# SIM7020_mp2128.net
KiCad netlist of a schematic drawn in Altium Designer
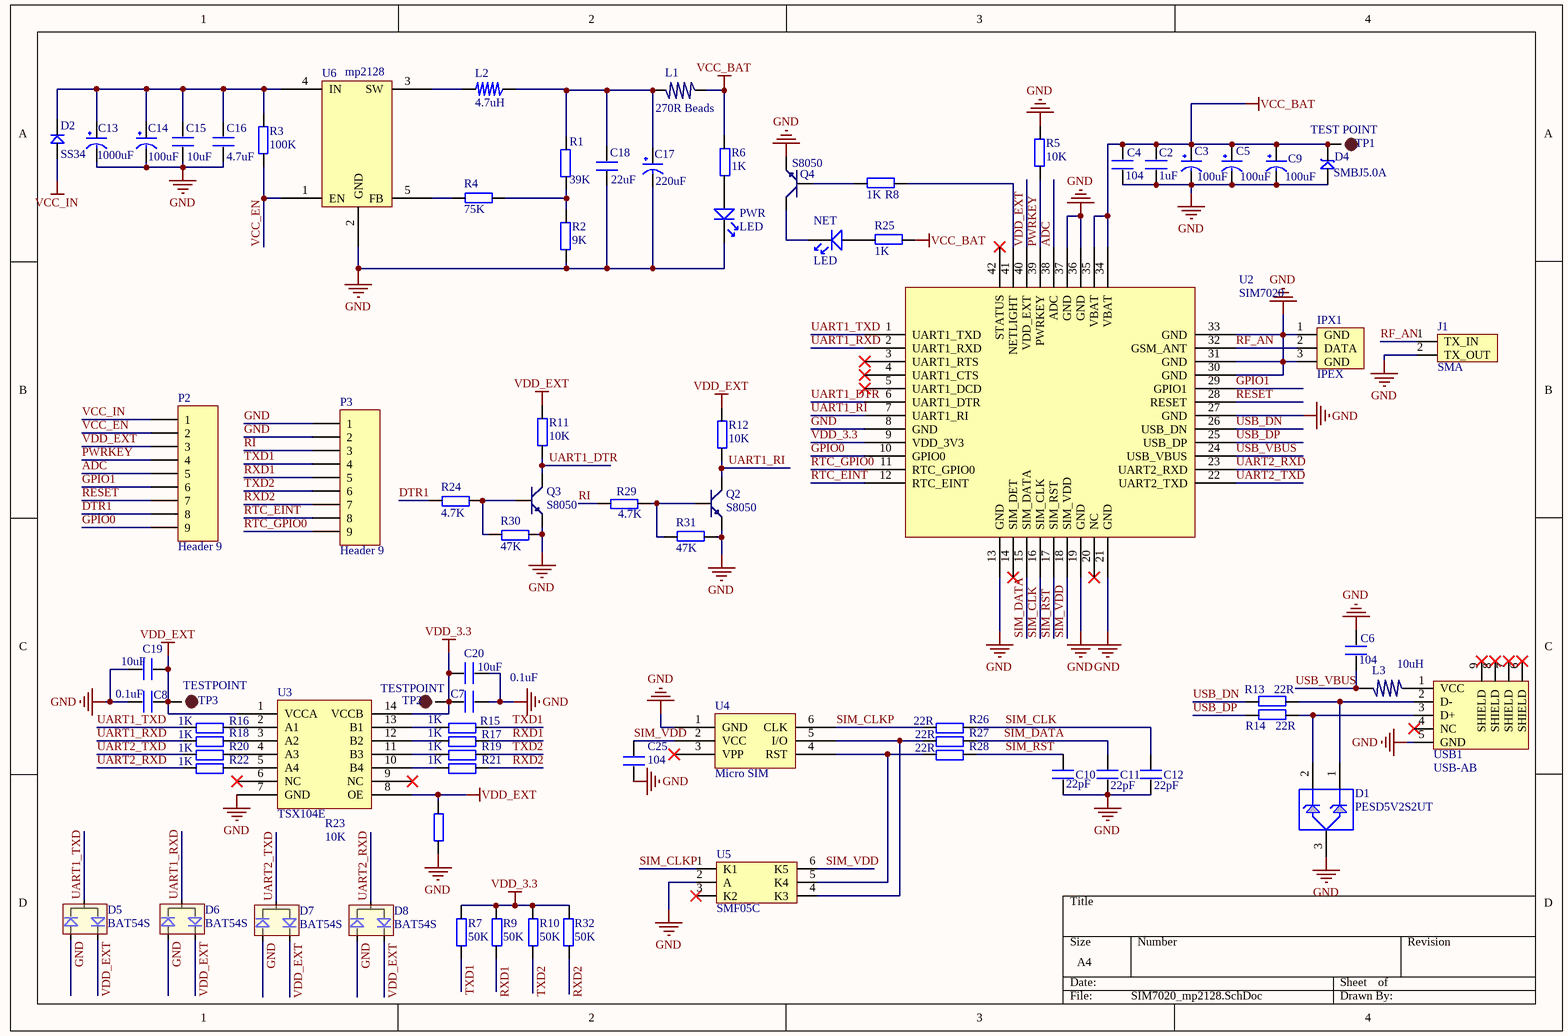
[diagram p0: SIM7020_mp2128.SchDoc]

(export (version "E")
  (design (tool "Eeschema 10.0.6"))
  (components
    (comp (ref "C2") (value "1uF") (footprint "0603P") (libsource (lib "SIM7020") (part "C")))
    (comp (ref "C3") (value "100uF") (footprint "C3528") (libsource (lib "SIM7020") (part "CAP")))
    (comp (ref "C4") (value "104") (footprint "0603P") (libsource (lib "ALIENTEK_COMPONENT") (part "C")))
    (comp (ref "C5") (value "100uF") (footprint "C3528") (libsource (lib "SIM7020") (part "CAP")))
    (comp (ref "C6") (value "104") (footprint "0603P") (libsource (lib "ALIENTEK_COMPONENT") (part "C")))
    (comp (ref "C7") (value "0.1uF") (footprint "0603P") (libsource (lib "SIM7020") (part "C")))
    (comp (ref "C8") (value "0.1uF") (footprint "0603P") (libsource (lib "SIM7020") (part "C")))
    (comp (ref "C9") (value "100uF") (footprint "C3528") (libsource (lib "SIM7020") (part "CAP")))
    (comp (ref "C10") (value "22pF") (footprint "0402") (libsource (lib "ALIENTEK_COMPONENT") (part "C")))
    (comp (ref "C11") (value "22pF") (footprint "0402") (libsource (lib "ALIENTEK_COMPONENT") (part "C")))
    (comp (ref "C12") (value "22pF") (footprint "0402") (libsource (lib "ALIENTEK_COMPONENT") (part "C")))
    (comp (ref "C13")
      (value "1000uF")
      (footprint "CAP2.54")
      (libsource (lib "ALIENTEK_COMPONENT") (part "CAP"))
    )
    (comp (ref "C14") (value "100uF") (footprint "C3528") (libsource (lib "ALIENTEK_COMPONENT") (part "CAP")))
    (comp (ref "C15") (value "10uF") (footprint "0805") (libsource (lib "SIM7020") (part "C")))
    (comp (ref "C16") (value "4.7uF") (footprint "0603P") (libsource (lib "SIM7020") (part "C")))
    (comp (ref "C17") (value "220uF") (footprint "CC6.56.5") (libsource (lib "SIM7020") (part "CAP")))
    (comp (ref "C18") (value "22uF") (footprint "1206") (libsource (lib "SIM7020") (part "C")))
    (comp (ref "C19") (value "10uF") (footprint "0603P") (libsource (lib "SIM7020") (part "C")))
    (comp (ref "C20") (value "10uF") (footprint "0603P") (libsource (lib "SIM7020") (part "C")))
    (comp (ref "C25") (value "104") (footprint "0603P") (libsource (lib "ALIENTEK_COMPONENT") (part "C")))
    (comp (ref "D1")
      (value "PESD5V2S2UT")
      (footprint "SOT-23")
      (description "PESD5V2S2UT,SOT-23,NXP")
      (fields (field (name "Comment") "ESD-3"))
      (libsource (lib "02.MCU_KL25") (part "ESD-3"))
    )
    (comp (ref "D2")
      (value "SS34")
      (footprint "DIODE_3*5.3")
      (description "1N4148")
      (libsource (lib "alientek_sch_lib") (part "D"))
    )
    (comp (ref "D4")
      (value "SMBJ5.0A")
      (footprint "SMBJ")
      (description "TVS")
      (libsource (lib "ALIENTEK_COMPONENT") (part "SMBJ"))
    )
    (comp (ref "D5")
      (value "BAT54S")
      (footprint "SOT-23")
      (description "双肖特基二极管")
      (libsource (lib "ALIENTEK_COMPONENT") (part "BAT54S"))
    )
    (comp (ref "D6")
      (value "BAT54S")
      (footprint "SOT-23")
      (description "双肖特基二极管")
      (libsource (lib "ALIENTEK_COMPONENT") (part "BAT54S"))
    )
    (comp (ref "D7")
      (value "BAT54S")
      (footprint "SOT-23")
      (description "双肖特基二极管")
      (libsource (lib "ALIENTEK_COMPONENT") (part "BAT54S"))
    )
    (comp (ref "D8")
      (value "BAT54S")
      (footprint "SOT-23")
      (description "双肖特基二极管")
      (libsource (lib "ALIENTEK_COMPONENT") (part "BAT54S"))
    )
    (comp (ref "IPX1")
      (value "IPEX")
      (footprint "IPEX")
      (description "IPEX座")
      (libsource (lib "ATK_S1216F8_BD_V1.1") (part "IPEX"))
    )
    (comp (ref "J1")
      (value "SMA")
      (footprint "SMA-2")
      (description "SMA-2")
      (libsource (lib "SIM7020") (part "SMA-2"))
    )
    (comp (ref "L1") (value "270R Beads") (footprint "1206") (libsource (lib "SIM7020") (part "L")))
    (comp (ref "L2")
      (value "4.7uH")
      (footprint "L_CD43")
      (libsource (lib "ATK-7'TFTLCD电容触摸屏模块_V2.2") (part "L_SOP"))
    )
    (comp (ref "L3") (value "10uH") (footprint "0805") (libsource (lib "ALIENTEK_COMPONENT") (part "L")))
    (comp (ref "NET") (value "LED") (footprint "SMDLED") (libsource (lib "SIM7020") (part "LED")))
    (comp (ref "P2")
      (value "Header 9")
      (footprint "HDR1X9")
      (description "Header, 9-Pin")
      (fields (field (name "PUBLISHER") "Altium Limited"))
      (libsource (lib "Miscellaneous Connectors") (part "Header 9"))
    )
    (comp (ref "P3")
      (value "Header 9")
      (footprint "HDR1X9")
      (description "Header, 9-Pin")
      (fields (field (name "PUBLISHER") "Altium Limited"))
      (libsource (lib "Miscellaneous Connectors") (part "Header 9"))
    )
    (comp (ref "PWR") (value "LED") (footprint "SMDLED") (libsource (lib "SIM7020") (part "LED")))
    (comp (ref "Q2")
      (value "S8050")
      (footprint "SOT-23R")
      (description "8050/BCW846/BCW847")
      (libsource (lib "SIM7020") (part "NPN"))
    )
    (comp (ref "Q3")
      (value "S8050")
      (footprint "SOT-23R")
      (description "8050/BCW846/BCW847")
      (libsource (lib "SIM7020") (part "NPN"))
    )
    (comp (ref "Q4")
      (value "S8050")
      (footprint "SOT-23R")
      (description "8050/BCW846/BCW847")
      (libsource (lib "SIM7020") (part "NPN"))
    )
    (comp (ref "R1") (value "39K") (footprint "0603P") (libsource (lib "ALIENTEK_COMPONENT") (part "R")))
    (comp (ref "R2") (value "9K") (footprint "0603P") (libsource (lib "ALIENTEK_COMPONENT") (part "R")))
    (comp (ref "R3") (value "100K") (footprint "0603P") (libsource (lib "ALIENTEK_COMPONENT") (part "R")))
    (comp (ref "R4") (value "75K") (footprint "0603P") (libsource (lib "ALIENTEK_COMPONENT") (part "R")))
    (comp (ref "R5") (value "10K") (footprint "0603P") (libsource (lib "ALIENTEK_COMPONENT") (part "R")))
    (comp (ref "R6") (value "1K") (footprint "0603P") (libsource (lib "ALIENTEK_COMPONENT") (part "R")))
    (comp (ref "R7") (value "50K") (footprint "0603P") (libsource (lib "SIM7020") (part "R")))
    (comp (ref "R8") (value "1K") (footprint "0603P") (libsource (lib "ALIENTEK_COMPONENT") (part "R")))
    (comp (ref "R9") (value "50K") (footprint "0603P") (libsource (lib "SIM7020") (part "R")))
    (comp (ref "R10") (value "50K") (footprint "0603P") (libsource (lib "SIM7020") (part "R")))
    (comp (ref "R11") (value "10K") (footprint "0603P") (libsource (lib "ALIENTEK_COMPONENT") (part "R")))
    (comp (ref "R12") (value "10K") (footprint "0603P") (libsource (lib "ALIENTEK_COMPONENT") (part "R")))
    (comp (ref "R13") (value "22R") (footprint "0603P") (libsource (lib "SIM7020") (part "R")))
    (comp (ref "R14") (value "22R") (footprint "0603P") (libsource (lib "SIM7020") (part "R")))
    (comp (ref "R15") (value "1K") (footprint "0603P") (libsource (lib "SIM7020") (part "R")))
    (comp (ref "R16") (value "1K") (footprint "0603P") (libsource (lib "SIM7020") (part "R")))
    (comp (ref "R17") (value "1K") (footprint "0603P") (libsource (lib "SIM7020") (part "R")))
    (comp (ref "R18") (value "1K") (footprint "0603P") (libsource (lib "SIM7020") (part "R")))
    (comp (ref "R19") (value "1K") (footprint "0603P") (libsource (lib "SIM7020") (part "R")))
    (comp (ref "R20") (value "1K") (footprint "0603P") (libsource (lib "SIM7020") (part "R")))
    (comp (ref "R21") (value "1K") (footprint "0603P") (libsource (lib "SIM7020") (part "R")))
    (comp (ref "R22") (value "1K") (footprint "0603P") (libsource (lib "SIM7020") (part "R")))
    (comp (ref "R23") (value "10K") (footprint "0603P") (libsource (lib "SIM7020") (part "R")))
    (comp (ref "R24") (value "4.7K") (footprint "0603P") (libsource (lib "ALIENTEK_COMPONENT") (part "R")))
    (comp (ref "R25") (value "1K") (footprint "0603P") (libsource (lib "ALIENTEK_COMPONENT") (part "R")))
    (comp (ref "R26") (value "22R") (footprint "0603P") (libsource (lib "SIM7020") (part "R")))
    (comp (ref "R27") (value "22R") (footprint "0603P") (libsource (lib "SIM7020") (part "R")))
    (comp (ref "R28") (value "22R") (footprint "0603P") (libsource (lib "SIM7020") (part "R")))
    (comp (ref "R29") (value "4.7K") (footprint "0603P") (libsource (lib "ALIENTEK_COMPONENT") (part "R")))
    (comp (ref "R30") (value "47K") (footprint "0603P") (libsource (lib "ALIENTEK_COMPONENT") (part "R")))
    (comp (ref "R31") (value "47K") (footprint "0603P") (libsource (lib "ALIENTEK_COMPONENT") (part "R")))
    (comp (ref "R32") (value "50K") (footprint "0603P") (libsource (lib "SIM7020") (part "R")))
    (comp (ref "TP1")
      (value "TEST POINT")
      (footprint "TP-1.5")
      (description "测试点")
      (libsource (lib "ALIENTEK_COMPONENT") (part "TEST-POINT"))
    )
    (comp (ref "TP2")
      (value "TESTPOINT")
      (footprint "TP-1.5")
      (description "测试点")
      (libsource (lib "ALIENTEK_COMPONENT") (part "TEST-POINT"))
    )
    (comp (ref "TP3")
      (value "TESTPOINT")
      (footprint "TP-1.5")
      (description "测试点")
      (libsource (lib "ALIENTEK_COMPONENT") (part "TEST-POINT"))
    )
    (comp (ref "U2")
      (value "SIM7020")
      (footprint "SIM7020")
      (description "NBloT")
      (libsource (lib "SIM7020") (part "SIM7020"))
    )
    (comp (ref "U3") (value "TSX104E") (footprint "TSX104E") (libsource (lib "SIM7020") (part "TSX104E")))
    (comp (ref "U4") (value "Micro SIM") (footprint "Micro SIM") (libsource (lib "plib") (part "Micro SIM")))
    (comp (ref "U5")
      (value "SMF05C")
      (footprint "SMF05C")
      (description "TVS")
      (libsource (lib "plib") (part "SMF05C"))
    )
    (comp (ref "U6") (value "mp2128") (footprint "SOT-23-5") (libsource (lib "SIM7020") (part "mp2128")))
    (comp (ref "USB1")
      (value "USB-AB")
      (footprint "USB_AB")
      (description "MicroUSB")
      (libsource (lib "ALIENTEK_COMPONENT") (part "USB-AB"))
    )
  )
  (nets
    (net (code "1") (name "/ADC") (class "Default")
      (node (ref "P2") (pin "5") (pinfunction "5_5") (pintype "passive"))
      (node (ref "U2") (pin "38") (pinfunction "ADC_38") (pintype "passive"))
    )
    (net (code "2") (name "/DTR1") (class "Default")
      (node (ref "P2") (pin "8") (pinfunction "8_8") (pintype "passive"))
      (node (ref "R24") (pin "1") (pintype "passive"))
    )
    (net (code "3") (name "/GPIO0") (class "Default")
      (node (ref "P2") (pin "9") (pinfunction "9_9") (pintype "passive"))
      (node (ref "U2") (pin "10") (pinfunction "GPIO0_10") (pintype "passive"))
    )
    (net (code "4") (name "/GPIO1") (class "Default")
      (node (ref "P2") (pin "6") (pinfunction "6_6") (pintype "passive"))
      (node (ref "U2") (pin "29") (pinfunction "GPIO1_29") (pintype "passive"))
    )
    (net (code "5") (name "/PWRKEY") (class "Default")
      (node (ref "P2") (pin "4") (pinfunction "4_4") (pintype "passive"))
      (node (ref "R5") (pin "2") (pintype "passive"))
      (node (ref "U2") (pin "39") (pinfunction "PWRKEY_39") (pintype "passive"))
    )
    (net (code "6") (name "/RESET") (class "Default")
      (node (ref "P2") (pin "7") (pinfunction "7_7") (pintype "passive"))
      (node (ref "U2") (pin "28") (pinfunction "RESET_28") (pintype "passive"))
    )
    (net (code "7") (name "/RF_AN") (class "Default")
      (node (ref "IPX1") (pin "2") (pinfunction "DATA_2") (pintype "passive"))
      (node (ref "J1") (pin "1") (pinfunction "TX_IN_1") (pintype "passive"))
      (node (ref "U2") (pin "32") (pinfunction "GSM_ANT_32") (pintype "passive"))
    )
    (net (code "8") (name "/RI") (class "Default")
      (node (ref "P3") (pin "3") (pinfunction "3_3") (pintype "passive"))
      (node (ref "R29") (pin "1") (pintype "passive"))
    )
    (net (code "9") (name "/RTC_EINT") (class "Default")
      (node (ref "P3") (pin "8") (pinfunction "8_8") (pintype "passive"))
      (node (ref "U2") (pin "12") (pinfunction "RTC_EINT_12") (pintype "passive"))
    )
    (net (code "10") (name "/RTC_GPIO0") (class "Default")
      (node (ref "P3") (pin "9") (pinfunction "9_9") (pintype "passive"))
      (node (ref "U2") (pin "11") (pinfunction "RTC_GPIO0_11") (pintype "passive"))
    )
    (net (code "11") (name "/RXD1") (class "Default")
      (node (ref "P3") (pin "5") (pinfunction "5_5") (pintype "passive"))
      (node (ref "R17") (pin "2") (pintype "passive"))
      (node (ref "R9") (pin "1") (pintype "passive"))
    )
    (net (code "12") (name "/RXD2") (class "Default")
      (node (ref "P3") (pin "7") (pinfunction "7_7") (pintype "passive"))
      (node (ref "R21") (pin "2") (pintype "passive"))
      (node (ref "R32") (pin "2") (pintype "passive"))
    )
    (net (code "13") (name "/SIM_CLK") (class "Default")
      (node (ref "C12") (pin "2") (pintype "passive"))
      (node (ref "R26") (pin "2") (pintype "passive"))
      (node (ref "U2") (pin "16") (pinfunction "SIM_CLK_16") (pintype "passive"))
    )
    (net (code "14") (name "/SIM_CLKP") (class "Default")
      (node (ref "R26") (pin "1") (pintype "passive"))
      (node (ref "U4") (pin "6") (pinfunction "CLK_6") (pintype "passive"))
      (node (ref "U5") (pin "1") (pinfunction "K1_1") (pintype "passive"))
    )
    (net (code "15") (name "/SIM_DATA") (class "Default")
      (node (ref "C11") (pin "2") (pintype "passive"))
      (node (ref "R27") (pin "2") (pintype "passive"))
      (node (ref "U2") (pin "15") (pinfunction "SIM_DATA_15") (pintype "passive"))
    )
    (net (code "16") (name "/SIM_RST") (class "Default")
      (node (ref "C10") (pin "1") (pintype "passive"))
      (node (ref "R28") (pin "2") (pintype "passive"))
      (node (ref "U2") (pin "17") (pinfunction "SIM_RST_17") (pintype "passive"))
    )
    (net (code "17") (name "/SIM_VDD") (class "Default")
      (node (ref "C25") (pin "2") (pintype "passive"))
      (node (ref "U2") (pin "18") (pinfunction "SIM_VDD_18") (pintype "passive"))
      (node (ref "U4") (pin "2") (pinfunction "VCC_2") (pintype "passive"))
      (node (ref "U5") (pin "6") (pinfunction "K5_6") (pintype "passive"))
    )
    (net (code "18") (name "/TXD1") (class "Default")
      (node (ref "P3") (pin "4") (pinfunction "4_4") (pintype "passive"))
      (node (ref "R15") (pin "2") (pintype "passive"))
      (node (ref "R7") (pin "1") (pintype "passive"))
    )
    (net (code "19") (name "/TXD2") (class "Default")
      (node (ref "P3") (pin "6") (pinfunction "6_6") (pintype "passive"))
      (node (ref "R10") (pin "1") (pintype "passive"))
      (node (ref "R19") (pin "2") (pintype "passive"))
    )
    (net (code "20") (name "/UART1_DTR") (class "Default")
      (node (ref "Q3") (pin "3") (pinfunction "C_3") (pintype "passive"))
      (node (ref "R11") (pin "1") (pintype "passive"))
      (node (ref "U2") (pin "6") (pinfunction "UART1_DTR_6") (pintype "passive"))
    )
    (net (code "21") (name "/UART1_RI") (class "Default")
      (node (ref "Q2") (pin "3") (pinfunction "C_3") (pintype "passive"))
      (node (ref "R12") (pin "1") (pintype "passive"))
      (node (ref "U2") (pin "7") (pinfunction "UART1_RI_7") (pintype "passive"))
    )
    (net (code "22") (name "/UART1_RXD") (class "Default")
      (node (ref "D6") (pin "3") (pintype "passive"))
      (node (ref "R18") (pin "1") (pintype "passive"))
      (node (ref "U2") (pin "2") (pinfunction "UART1_RXD_2") (pintype "passive"))
    )
    (net (code "23") (name "/UART1_TXD") (class "Default")
      (node (ref "D5") (pin "3") (pintype "passive"))
      (node (ref "R16") (pin "1") (pintype "passive"))
      (node (ref "U2") (pin "1") (pinfunction "UART1_TXD_1") (pintype "passive"))
    )
    (net (code "24") (name "/UART2_RXD") (class "Default")
      (node (ref "D8") (pin "3") (pintype "passive"))
      (node (ref "R22") (pin "1") (pintype "passive"))
      (node (ref "U2") (pin "23") (pinfunction "UART2_RXD_23") (pintype "passive"))
    )
    (net (code "25") (name "/UART2_TXD") (class "Default")
      (node (ref "D7") (pin "3") (pintype "passive"))
      (node (ref "R20") (pin "1") (pintype "passive"))
      (node (ref "U2") (pin "22") (pinfunction "UART2_TXD_22") (pintype "passive"))
    )
    (net (code "26") (name "/USB_DN") (class "Default")
      (node (ref "R13") (pin "2") (pintype "passive"))
      (node (ref "U2") (pin "26") (pinfunction "USB_DN_26") (pintype "passive"))
    )
    (net (code "27") (name "/USB_DP") (class "Default")
      (node (ref "R14") (pin "2") (pintype "passive"))
      (node (ref "U2") (pin "25") (pinfunction "USB_DP_25") (pintype "passive"))
    )
    (net (code "28") (name "/USB_VBUS") (class "Default")
      (node (ref "C6") (pin "1") (pintype "passive"))
      (node (ref "L3") (pin "2") (pintype "passive"))
      (node (ref "U2") (pin "24") (pinfunction "USB_VBUS_24") (pintype "passive"))
    )
    (net (code "29") (name "/VCC_EN") (class "Default")
      (node (ref "P2") (pin "2") (pinfunction "2_2") (pintype "passive"))
      (node (ref "R3") (pin "2") (pintype "passive"))
      (node (ref "U6") (pin "1") (pinfunction "EN_1") (pintype "passive"))
    )
    (net (code "30") (name "GND") (class "Default")
      (node (ref "C10") (pin "2") (pintype "passive"))
      (node (ref "C11") (pin "1") (pintype "passive"))
      (node (ref "C12") (pin "1") (pintype "passive"))
      (node (ref "C13") (pin "2") (pinfunction "GND_2") (pintype "passive"))
      (node (ref "C14") (pin "2") (pinfunction "GND_2") (pintype "passive"))
      (node (ref "C15") (pin "2") (pintype "passive"))
      (node (ref "C16") (pin "1") (pintype "passive"))
      (node (ref "C17") (pin "2") (pinfunction "GND_2") (pintype "passive"))
      (node (ref "C18") (pin "1") (pintype "passive"))
      (node (ref "C19") (pin "2") (pintype "passive"))
      (node (ref "C2") (pin "1") (pintype "passive"))
      (node (ref "C20") (pin "2") (pintype "passive"))
      (node (ref "C25") (pin "1") (pintype "passive"))
      (node (ref "C3") (pin "2") (pinfunction "GND_2") (pintype "passive"))
      (node (ref "C4") (pin "1") (pintype "passive"))
      (node (ref "C5") (pin "2") (pinfunction "GND_2") (pintype "passive"))
      (node (ref "C6") (pin "2") (pintype "passive"))
      (node (ref "C7") (pin "2") (pintype "passive"))
      (node (ref "C8") (pin "2") (pintype "passive"))
      (node (ref "C9") (pin "2") (pinfunction "GND_2") (pintype "passive"))
      (node (ref "D1") (pin "3") (pinfunction "3_3") (pintype "passive"))
      (node (ref "D4") (pin "1") (pintype "passive"))
      (node (ref "D5") (pin "1") (pintype "passive"))
      (node (ref "D6") (pin "1") (pintype "passive"))
      (node (ref "D7") (pin "1") (pintype "passive"))
      (node (ref "D8") (pin "1") (pintype "passive"))
      (node (ref "IPX1") (pin "1") (pinfunction "GND_1") (pintype "passive"))
      (node (ref "IPX1") (pin "3") (pinfunction "GND_3") (pintype "passive"))
      (node (ref "J1") (pin "2") (pinfunction "TX_OUT_2") (pintype "passive"))
      (node (ref "P3") (pin "1") (pinfunction "1_1") (pintype "passive"))
      (node (ref "P3") (pin "2") (pinfunction "2_2") (pintype "passive"))
      (node (ref "PWR") (pin "2") (pinfunction "2_2") (pintype "passive"))
      (node (ref "Q2") (pin "1") (pinfunction "E_1") (pintype "passive"))
      (node (ref "Q3") (pin "1") (pinfunction "E_1") (pintype "passive"))
      (node (ref "Q4") (pin "1") (pinfunction "E_1") (pintype "passive"))
      (node (ref "R2") (pin "2") (pintype "passive"))
      (node (ref "R23") (pin "1") (pintype "passive"))
      (node (ref "R30") (pin "2") (pintype "passive"))
      (node (ref "R31") (pin "1") (pintype "passive"))
      (node (ref "R5") (pin "1") (pintype "passive"))
      (node (ref "U2") (pin "13") (pinfunction "GND_13") (pintype "passive"))
      (node (ref "U2") (pin "19") (pinfunction "GND_19") (pintype "passive"))
      (node (ref "U2") (pin "21") (pinfunction "GND_21") (pintype "passive"))
      (node (ref "U2") (pin "27") (pinfunction "GND_27") (pintype "passive"))
      (node (ref "U2") (pin "30") (pinfunction "GND_30") (pintype "passive"))
      (node (ref "U2") (pin "31") (pinfunction "GND_31") (pintype "passive"))
      (node (ref "U2") (pin "33") (pinfunction "GND_33") (pintype "passive"))
      (node (ref "U2") (pin "36") (pinfunction "GND_36") (pintype "passive"))
      (node (ref "U2") (pin "37") (pinfunction "GND_37") (pintype "passive"))
      (node (ref "U2") (pin "8") (pinfunction "GND_8") (pintype "passive"))
      (node (ref "U3") (pin "7") (pinfunction "GND_7") (pintype "passive"))
      (node (ref "U4") (pin "1") (pinfunction "GND_1") (pintype "passive"))
      (node (ref "U5") (pin "2") (pinfunction "A_2") (pintype "passive"))
      (node (ref "U6") (pin "2") (pinfunction "GND_2") (pintype "passive"))
      (node (ref "USB1") (pin "5") (pinfunction "GND_5") (pintype "passive"))
    )
    (net (code "31") (name "Net-(C13-VCC)") (class "Default")
      (node (ref "C13") (pin "1") (pinfunction "VCC_1") (pintype "passive"))
      (node (ref "C14") (pin "1") (pinfunction "VCC_1") (pintype "passive"))
      (node (ref "C15") (pin "1") (pintype "passive"))
      (node (ref "C16") (pin "2") (pintype "passive"))
      (node (ref "D2") (pin "2") (pintype "passive"))
      (node (ref "R3") (pin "1") (pintype "passive"))
      (node (ref "U6") (pin "4") (pinfunction "IN_4") (pintype "passive"))
    )
    (net (code "32") (name "Net-(C17-VCC)") (class "Default")
      (node (ref "C17") (pin "1") (pinfunction "VCC_1") (pintype "passive"))
      (node (ref "C18") (pin "2") (pintype "passive"))
      (node (ref "L1") (pin "2") (pintype "passive"))
      (node (ref "L2") (pin "1") (pinfunction "1_1") (pintype "passive"))
      (node (ref "R1") (pin "1") (pintype "passive"))
    )
    (net (code "33") (name "Net-(NET-Pad1)") (class "Default")
      (node (ref "NET") (pin "1") (pinfunction "1_1") (pintype "passive"))
      (node (ref "R25") (pin "2") (pintype "passive"))
    )
    (net (code "34") (name "Net-(PWR-Pad1)") (class "Default")
      (node (ref "PWR") (pin "1") (pinfunction "1_1") (pintype "passive"))
      (node (ref "R6") (pin "1") (pintype "passive"))
    )
    (net (code "35") (name "Net-(Q2-B)") (class "Default")
      (node (ref "Q2") (pin "2") (pinfunction "B_2") (pintype "passive"))
      (node (ref "R29") (pin "2") (pintype "passive"))
      (node (ref "R31") (pin "2") (pintype "passive"))
    )
    (net (code "36") (name "Net-(Q3-B)") (class "Default")
      (node (ref "Q3") (pin "2") (pinfunction "B_2") (pintype "passive"))
      (node (ref "R24") (pin "2") (pintype "passive"))
      (node (ref "R30") (pin "1") (pintype "passive"))
    )
    (net (code "37") (name "Net-(Q4-B)") (class "Default")
      (node (ref "Q4") (pin "2") (pinfunction "B_2") (pintype "passive"))
      (node (ref "R8") (pin "2") (pintype "passive"))
    )
    (net (code "38") (name "Net-(Q4-C)") (class "Default")
      (node (ref "NET") (pin "2") (pinfunction "2_2") (pintype "passive"))
      (node (ref "Q4") (pin "3") (pinfunction "C_3") (pintype "passive"))
    )
    (net (code "39") (name "Net-(R1-Pad2)") (class "Default")
      (node (ref "R1") (pin "2") (pintype "passive"))
      (node (ref "R2") (pin "1") (pintype "passive"))
      (node (ref "R4") (pin "1") (pintype "passive"))
    )
    (net (code "40") (name "Net-(U2-NETLIGHT)") (class "Default")
      (node (ref "R8") (pin "1") (pintype "passive"))
      (node (ref "U2") (pin "41") (pinfunction "NETLIGHT_41") (pintype "passive"))
    )
    (net (code "41") (name "Net-(U3-A1)") (class "Default")
      (node (ref "R16") (pin "2") (pintype "passive"))
      (node (ref "U3") (pin "2") (pinfunction "A1_2") (pintype "passive"))
    )
    (net (code "42") (name "Net-(U3-A2)") (class "Default")
      (node (ref "R18") (pin "2") (pintype "passive"))
      (node (ref "U3") (pin "3") (pinfunction "A2_3") (pintype "passive"))
    )
    (net (code "43") (name "Net-(U3-A3)") (class "Default")
      (node (ref "R20") (pin "2") (pintype "passive"))
      (node (ref "U3") (pin "4") (pinfunction "A3_4") (pintype "passive"))
    )
    (net (code "44") (name "Net-(U3-A4)") (class "Default")
      (node (ref "R22") (pin "2") (pintype "passive"))
      (node (ref "U3") (pin "5") (pinfunction "A4_5") (pintype "passive"))
    )
    (net (code "45") (name "Net-(U3-B1)") (class "Default")
      (node (ref "R15") (pin "1") (pintype "passive"))
      (node (ref "U3") (pin "13") (pinfunction "B1_13") (pintype "passive"))
    )
    (net (code "46") (name "Net-(U3-B2)") (class "Default")
      (node (ref "R17") (pin "1") (pintype "passive"))
      (node (ref "U3") (pin "12") (pinfunction "B2_12") (pintype "passive"))
    )
    (net (code "47") (name "Net-(U3-B3)") (class "Default")
      (node (ref "R19") (pin "1") (pintype "passive"))
      (node (ref "U3") (pin "11") (pinfunction "B3_11") (pintype "passive"))
    )
    (net (code "48") (name "Net-(U3-B4)") (class "Default")
      (node (ref "R21") (pin "1") (pintype "passive"))
      (node (ref "U3") (pin "10") (pinfunction "B4_10") (pintype "passive"))
    )
    (net (code "49") (name "Net-(U4-I{slash}O)") (class "Default")
      (node (ref "R27") (pin "1") (pintype "passive"))
      (node (ref "U4") (pin "5") (pinfunction "I/O_5") (pintype "passive"))
      (node (ref "U5") (pin "4") (pinfunction "K3_4") (pintype "passive"))
    )
    (net (code "50") (name "Net-(U4-RST)") (class "Default")
      (node (ref "R28") (pin "1") (pintype "passive"))
      (node (ref "U4") (pin "4") (pinfunction "RST_4") (pintype "passive"))
      (node (ref "U5") (pin "5") (pinfunction "K4_5") (pintype "passive"))
    )
    (net (code "51") (name "Net-(U6-FB)") (class "Default")
      (node (ref "R4") (pin "2") (pintype "passive"))
      (node (ref "U6") (pin "5") (pinfunction "FB_5") (pintype "passive"))
    )
    (net (code "52") (name "Net-(U6-SW)") (class "Default")
      (node (ref "L2") (pin "2") (pinfunction "2_2") (pintype "passive"))
      (node (ref "U6") (pin "3") (pinfunction "SW_3") (pintype "passive"))
    )
    (net (code "53") (name "Net-(USB1-D+)") (class "Default")
      (node (ref "D1") (pin "2") (pinfunction "2_2") (pintype "passive"))
      (node (ref "R14") (pin "1") (pintype "passive"))
      (node (ref "USB1") (pin "3") (pinfunction "D+_3") (pintype "passive"))
    )
    (net (code "54") (name "Net-(USB1-D-)") (class "Default")
      (node (ref "D1") (pin "1") (pinfunction "1_1") (pintype "passive"))
      (node (ref "R13") (pin "1") (pintype "passive"))
      (node (ref "USB1") (pin "2") (pinfunction "D-_2") (pintype "passive"))
    )
    (net (code "55") (name "Net-(USB1-VCC)") (class "Default")
      (node (ref "L3") (pin "1") (pintype "passive"))
      (node (ref "USB1") (pin "1") (pinfunction "VCC_1") (pintype "passive"))
    )
    (net (code "56") (name "VCC_BAT") (class "Default")
      (node (ref "C2") (pin "2") (pintype "passive"))
      (node (ref "C3") (pin "1") (pinfunction "VCC_1") (pintype "passive"))
      (node (ref "C4") (pin "2") (pintype "passive"))
      (node (ref "C5") (pin "1") (pinfunction "VCC_1") (pintype "passive"))
      (node (ref "C9") (pin "1") (pinfunction "VCC_1") (pintype "passive"))
      (node (ref "D4") (pin "2") (pintype "passive"))
      (node (ref "L1") (pin "1") (pintype "passive"))
      (node (ref "R25") (pin "1") (pintype "passive"))
      (node (ref "R6") (pin "2") (pintype "passive"))
      (node (ref "TP1") (pin "1") (pinfunction "1_1") (pintype "passive"))
      (node (ref "U2") (pin "34") (pinfunction "VBAT_34") (pintype "passive"))
      (node (ref "U2") (pin "35") (pinfunction "VBAT_35") (pintype "passive"))
    )
    (net (code "57") (name "VCC_IN") (class "Default")
      (node (ref "D2") (pin "1") (pintype "passive"))
      (node (ref "P2") (pin "1") (pinfunction "1_1") (pintype "passive"))
    )
    (net (code "58") (name "VDD_3.3") (class "Default")
      (node (ref "C20") (pin "1") (pintype "passive"))
      (node (ref "C7") (pin "1") (pintype "passive"))
      (node (ref "R10") (pin "2") (pintype "passive"))
      (node (ref "R32") (pin "1") (pintype "passive"))
      (node (ref "R7") (pin "2") (pintype "passive"))
      (node (ref "R9") (pin "2") (pintype "passive"))
      (node (ref "TP2") (pin "1") (pinfunction "1_1") (pintype "passive"))
      (node (ref "U2") (pin "9") (pinfunction "VDD_3V3_9") (pintype "passive"))
      (node (ref "U3") (pin "14") (pinfunction "VCCB_14") (pintype "passive"))
    )
    (net (code "59") (name "VDD_EXT") (class "Default")
      (node (ref "C19") (pin "1") (pintype "passive"))
      (node (ref "C8") (pin "1") (pintype "passive"))
      (node (ref "D5") (pin "2") (pintype "passive"))
      (node (ref "D6") (pin "2") (pintype "passive"))
      (node (ref "D7") (pin "2") (pintype "passive"))
      (node (ref "D8") (pin "2") (pintype "passive"))
      (node (ref "P2") (pin "3") (pinfunction "3_3") (pintype "passive"))
      (node (ref "R11") (pin "2") (pintype "passive"))
      (node (ref "R12") (pin "2") (pintype "passive"))
      (node (ref "R23") (pin "2") (pintype "passive"))
      (node (ref "TP3") (pin "1") (pinfunction "1_1") (pintype "passive"))
      (node (ref "U2") (pin "40") (pinfunction "VDD_EXT_40") (pintype "passive"))
      (node (ref "U3") (pin "1") (pinfunction "VCCA_1") (pintype "passive"))
      (node (ref "U3") (pin "8") (pinfunction "OE_8") (pintype "passive"))
    )
    (net (code "60") (name "unconnected-(U2-NC-Pad20)") (class "Default")
      (node (ref "U2") (pin "20") (pinfunction "NC_20") (pintype "passive+no_connect"))
    )
    (net (code "61") (name "unconnected-(U2-SIM_DET-Pad14)") (class "Default")
      (node (ref "U2") (pin "14") (pinfunction "SIM_DET_14") (pintype "passive+no_connect"))
    )
    (net (code "62") (name "unconnected-(U2-STATUS-Pad42)") (class "Default")
      (node (ref "U2") (pin "42") (pinfunction "STATUS_42") (pintype "passive+no_connect"))
    )
    (net (code "63") (name "unconnected-(U2-UART1_CTS-Pad4)") (class "Default")
      (node (ref "U2") (pin "4") (pinfunction "UART1_CTS_4") (pintype "passive+no_connect"))
    )
    (net (code "64") (name "unconnected-(U2-UART1_DCD-Pad5)") (class "Default")
      (node (ref "U2") (pin "5") (pinfunction "UART1_DCD_5") (pintype "passive+no_connect"))
    )
    (net (code "65") (name "unconnected-(U2-UART1_RTS-Pad3)") (class "Default")
      (node (ref "U2") (pin "3") (pinfunction "UART1_RTS_3") (pintype "passive+no_connect"))
    )
    (net (code "66") (name "unconnected-(U3-NC-Pad6)") (class "Default")
      (node (ref "U3") (pin "6") (pinfunction "NC_6") (pintype "passive+no_connect"))
    )
    (net (code "67") (name "unconnected-(U3-NC-Pad9)") (class "Default")
      (node (ref "U3") (pin "9") (pinfunction "NC_9") (pintype "passive+no_connect"))
    )
    (net (code "68") (name "unconnected-(U4-VPP-Pad3)") (class "Default")
      (node (ref "U4") (pin "3") (pinfunction "VPP_3") (pintype "passive+no_connect"))
    )
    (net (code "69") (name "unconnected-(U5-K2-Pad3)") (class "Default")
      (node (ref "U5") (pin "3") (pinfunction "K2_3") (pintype "passive+no_connect"))
    )
    (net (code "70") (name "unconnected-(USB1-NC-Pad4)") (class "Default")
      (node (ref "USB1") (pin "4") (pinfunction "NC_4") (pintype "passive+no_connect"))
    )
    (net (code "71") (name "unconnected-(USB1-SHIELD-Pad6)") (class "Default")
      (node (ref "USB1") (pin "6") (pinfunction "SHIELD_6") (pintype "passive+no_connect"))
    )
    (net (code "72") (name "unconnected-(USB1-SHIELD-Pad7)") (class "Default")
      (node (ref "USB1") (pin "7") (pinfunction "SHIELD_7") (pintype "passive+no_connect"))
    )
    (net (code "73") (name "unconnected-(USB1-SHIELD-Pad8)") (class "Default")
      (node (ref "USB1") (pin "8") (pinfunction "SHIELD_8") (pintype "passive+no_connect"))
    )
    (net (code "74") (name "unconnected-(USB1-SHIELD-Pad9)") (class "Default")
      (node (ref "USB1") (pin "9") (pinfunction "SHIELD_9") (pintype "passive+no_connect"))
    )
  )
)
